# Shema.net
KiCad netlist of a schematic drawn in Altium Designer
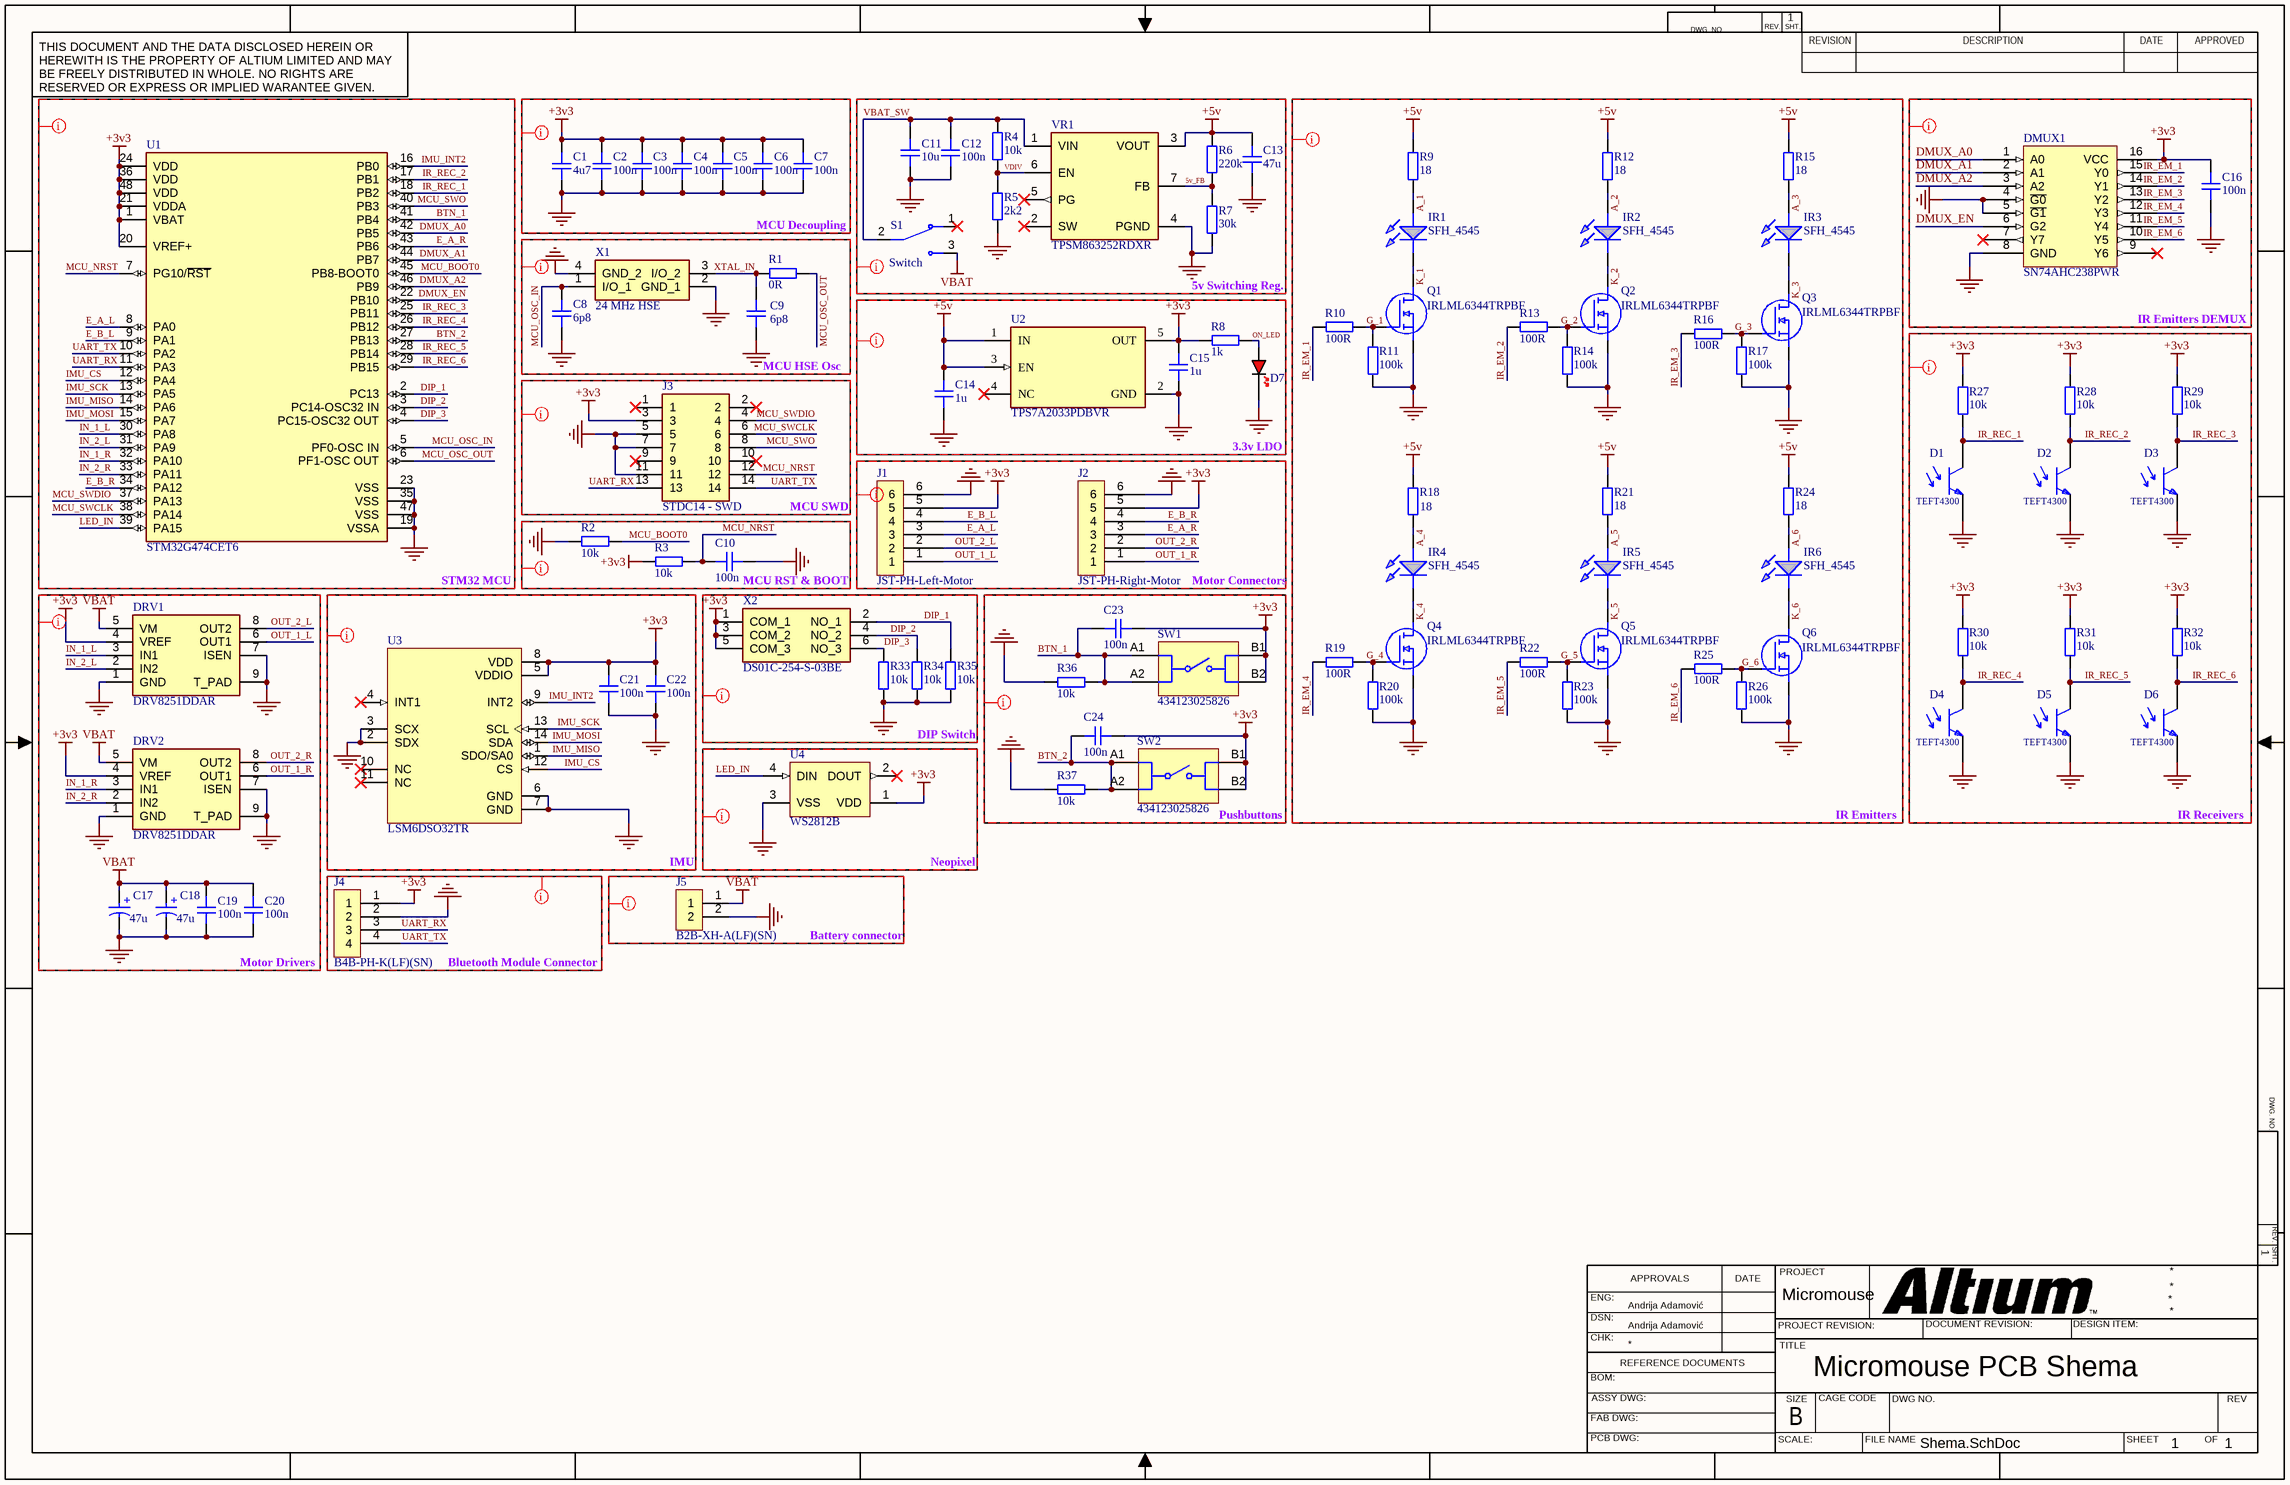
[diagram p0: Shema.SchDoc]

(export (version "E")
  (design (tool "Eeschema 10.0.6"))
  (components
    (comp (ref "C1")
      (value "4u7")
      (footprint "CAP_0603")
      (description "Capacitor SMD 0603")
      (libsource (lib "Schematic-Lib-PhilsLab") (part "CAP_0603"))
    )
    (comp (ref "C2")
      (value "100n")
      (footprint "CAP_0603")
      (description "Capacitor SMD 0603")
      (libsource (lib "Schematic-Lib-PhilsLab") (part "CAP_0603"))
    )
    (comp (ref "C3")
      (value "100n")
      (footprint "CAP_0603")
      (description "Capacitor SMD 0603")
      (libsource (lib "Schematic-Lib-PhilsLab") (part "CAP_0603"))
    )
    (comp (ref "C4")
      (value "100n")
      (footprint "CAP_0603")
      (description "Capacitor SMD 0603")
      (libsource (lib "Schematic-Lib-PhilsLab") (part "CAP_0603"))
    )
    (comp (ref "C5")
      (value "100n")
      (footprint "CAP_0603")
      (description "Capacitor SMD 0603")
      (libsource (lib "Schematic-Lib-PhilsLab") (part "CAP_0603"))
    )
    (comp (ref "C6")
      (value "100n")
      (footprint "CAP_0603")
      (description "Capacitor SMD 0603")
      (libsource (lib "Schematic-Lib-PhilsLab") (part "CAP_0603"))
    )
    (comp (ref "C7")
      (value "100n")
      (footprint "CAP_0603")
      (description "Capacitor SMD 0603")
      (libsource (lib "Schematic-Lib-PhilsLab") (part "CAP_0603"))
    )
    (comp (ref "C8")
      (value "6p8")
      (footprint "CAP_0603")
      (description "Capacitor SMD 0603")
      (libsource (lib "Schematic-Lib-PhilsLab") (part "CAP_0603"))
    )
    (comp (ref "C9")
      (value "6p8")
      (footprint "CAP_0603")
      (description "Capacitor SMD 0603")
      (libsource (lib "Schematic-Lib-PhilsLab") (part "CAP_0603"))
    )
    (comp (ref "C10")
      (value "100n")
      (footprint "CAP_0603")
      (description "Capacitor SMD 0603")
      (libsource (lib "Schematic-Lib-PhilsLab") (part "CAP_0603"))
    )
    (comp (ref "C11")
      (value "10u")
      (footprint "CAP_0805")
      (description "Capacitor SMD 0805")
      (libsource (lib "Schematic-Lib-PhilsLab") (part "CAP_0805"))
    )
    (comp (ref "C12")
      (value "100n")
      (footprint "CAP_0603")
      (description "Capacitor SMD 0603")
      (libsource (lib "Schematic-Lib-PhilsLab") (part "CAP_0603"))
    )
    (comp (ref "C13")
      (value "47u")
      (footprint "CAP_1206")
      (description "Capacitor SMD 1206")
      (libsource (lib "Schematic-Lib-PhilsLab") (part "CAP_1206"))
    )
    (comp (ref "C14")
      (value "1u")
      (footprint "CAP_0805")
      (description "Capacitor SMD 0805")
      (libsource (lib "Schematic-Lib-PhilsLab") (part "CAP_0805"))
    )
    (comp (ref "C15")
      (value "1u")
      (footprint "CAP_0805")
      (description "Capacitor SMD 0805")
      (libsource (lib "Schematic-Lib-PhilsLab") (part "CAP_0805"))
    )
    (comp (ref "C16")
      (value "100n")
      (footprint "CAP_0603")
      (description "Capacitor SMD 0603")
      (libsource (lib "Schematic-Lib-PhilsLab") (part "CAP_0603"))
    )
    (comp (ref "C17")
      (value "47u")
      (footprint "WCAP-ASLI_D6.3H5.5")
      (description "WCAP-ASLI Aluminum Electrolytic Capacitors")
      (fields (field (name "TOLERANCE") "20%"))
      (libsource (lib "Altium Content Vault") (part "Capacitor_Polarized"))
    )
    (comp (ref "C18")
      (value "47u")
      (footprint "WCAP-ASLI_D6.3H5.5")
      (description "WCAP-ASLI Aluminum Electrolytic Capacitors")
      (fields (field (name "TOLERANCE") "20%"))
      (libsource (lib "Altium Content Vault") (part "Capacitor_Polarized"))
    )
    (comp (ref "C19")
      (value "100n")
      (footprint "CAP_0603")
      (description "Capacitor SMD 0603")
      (libsource (lib "Schematic-Lib-PhilsLab") (part "CAP_0603"))
    )
    (comp (ref "C20")
      (value "100n")
      (footprint "CAP_0603")
      (description "Capacitor SMD 0603")
      (libsource (lib "Schematic-Lib-PhilsLab") (part "CAP_0603"))
    )
    (comp (ref "C21")
      (value "100n")
      (footprint "CAP_0603")
      (description "Capacitor SMD 0603")
      (libsource (lib "Schematic-Lib-PhilsLab") (part "CAP_0603"))
    )
    (comp (ref "C22")
      (value "100n")
      (footprint "CAP_0603")
      (description "Capacitor SMD 0603")
      (libsource (lib "Schematic-Lib-PhilsLab") (part "CAP_0603"))
    )
    (comp (ref "C23")
      (value "100n")
      (footprint "CAP_0603")
      (description "Capacitor SMD 0603")
      (libsource (lib "Schematic-Lib-PhilsLab") (part "CAP_0603"))
    )
    (comp (ref "C24")
      (value "100n")
      (footprint "CAP_0603")
      (description "Capacitor SMD 0603")
      (libsource (lib "Schematic-Lib-PhilsLab") (part "CAP_0603"))
    )
    (comp (ref "D1")
      (value "TEFT4300")
      (footprint "FP-6_544-5269_01-4-MFG")
      (description "TEFT4300 PHOTOTRANSISTOR 3.0MM WIDE VIEW / Phototransistor IR Chip Silicon 925nm 2-Pin T-1")
      (libsource (lib "Altium Content Vault") (part "fcf5d96e013ede1c9e051256f92411f"))
    )
    (comp (ref "D2")
      (value "TEFT4300")
      (footprint "FP-6_544-5269_01-4-MFG")
      (description "TEFT4300 PHOTOTRANSISTOR 3.0MM WIDE VIEW / Phototransistor IR Chip Silicon 925nm 2-Pin T-1")
      (libsource (lib "Altium Content Vault") (part "fcf5d96e013ede1c9e051256f92411f"))
    )
    (comp (ref "D3")
      (value "TEFT4300")
      (footprint "FP-6_544-5269_01-4-MFG")
      (description "TEFT4300 PHOTOTRANSISTOR 3.0MM WIDE VIEW / Phototransistor IR Chip Silicon 925nm 2-Pin T-1")
      (libsource (lib "Altium Content Vault") (part "fcf5d96e013ede1c9e051256f92411f"))
    )
    (comp (ref "D4")
      (value "TEFT4300")
      (footprint "FP-6_544-5269_01-4-MFG")
      (description "TEFT4300 PHOTOTRANSISTOR 3.0MM WIDE VIEW / Phototransistor IR Chip Silicon 925nm 2-Pin T-1")
      (libsource (lib "Altium Content Vault") (part "fcf5d96e013ede1c9e051256f92411f"))
    )
    (comp (ref "D5")
      (value "TEFT4300")
      (footprint "FP-6_544-5269_01-4-MFG")
      (description "TEFT4300 PHOTOTRANSISTOR 3.0MM WIDE VIEW / Phototransistor IR Chip Silicon 925nm 2-Pin T-1")
      (libsource (lib "Altium Content Vault") (part "fcf5d96e013ede1c9e051256f92411f"))
    )
    (comp (ref "D6")
      (value "TEFT4300")
      (footprint "FP-6_544-5269_01-4-MFG")
      (description "TEFT4300 PHOTOTRANSISTOR 3.0MM WIDE VIEW / Phototransistor IR Chip Silicon 925nm 2-Pin T-1")
      (libsource (lib "Altium Content Vault") (part "fcf5d96e013ede1c9e051256f92411f"))
    )
    (comp (ref "D7")
      (value "RED")
      (footprint "LED_0603_RED")
      (description "LED 0603 RED SMD")
      (libsource (lib "Schematic-Lib-PhilsLab") (part "LED_0603_RED"))
    )
    (comp (ref "DMUX1")
      (value "SN74AHC238PWR")
      (footprint "TSOP65P640X120-16N")
      (libsource (lib "Andrija Adamovic") (part "SN74AHC238PWR-Symbol-1"))
    )
    (comp (ref "DRV1")
      (value "DRV8251DDAR")
      (footprint "SOIC127P600X170-9N")
      (description "Motor Drives")
      (fields (field (name "MOUSER PART NUMBER") "595-DRV8251DDAR"))
      (libsource (lib "Andrija Adamovic") (part "DRV8251DDAR"))
    )
    (comp (ref "DRV2")
      (value "DRV8251DDAR")
      (footprint "SOIC127P600X170-9N")
      (description "Motor Drives")
      (fields (field (name "MOUSER PART NUMBER") "595-DRV8251DDAR"))
      (libsource (lib "Andrija Adamovic") (part "DRV8251DDAR"))
    )
    (comp (ref "IR1")
      (value "SFH_4545")
      (footprint "SFH4545")
      (description "SFH 4545 Osram Opto, 950nm IR LED, 5 mm Through Hole package")
      (fields
        (field (name "MANUFACTURER_PART_NUMBER") "SFH 4545")
        (field (name "MOUSER PART NUMBER") "720-SFH4545")
      )
      (libsource (lib "Andrija Adamovic") (part "SFH_4545"))
    )
    (comp (ref "IR2")
      (value "SFH_4545")
      (footprint "SFH4545")
      (description "SFH 4545 Osram Opto, 950nm IR LED, 5 mm Through Hole package")
      (fields
        (field (name "MANUFACTURER_PART_NUMBER") "SFH 4545")
        (field (name "MOUSER PART NUMBER") "720-SFH4545")
      )
      (libsource (lib "Andrija Adamovic") (part "SFH_4545"))
    )
    (comp (ref "IR3")
      (value "SFH_4545")
      (footprint "SFH4545")
      (description "SFH 4545 Osram Opto, 950nm IR LED, 5 mm Through Hole package")
      (fields
        (field (name "MANUFACTURER_PART_NUMBER") "SFH 4545")
        (field (name "MOUSER PART NUMBER") "720-SFH4545")
      )
      (libsource (lib "Andrija Adamovic") (part "SFH_4545"))
    )
    (comp (ref "IR4")
      (value "SFH_4545")
      (footprint "SFH4545")
      (description "SFH 4545 Osram Opto, 950nm IR LED, 5 mm Through Hole package")
      (fields
        (field (name "MANUFACTURER_PART_NUMBER") "SFH 4545")
        (field (name "MOUSER PART NUMBER") "720-SFH4545")
      )
      (libsource (lib "Andrija Adamovic") (part "SFH_4545"))
    )
    (comp (ref "IR5")
      (value "SFH_4545")
      (footprint "SFH4545")
      (description "SFH 4545 Osram Opto, 950nm IR LED, 5 mm Through Hole package")
      (fields
        (field (name "MANUFACTURER_PART_NUMBER") "SFH 4545")
        (field (name "MOUSER PART NUMBER") "720-SFH4545")
      )
      (libsource (lib "Andrija Adamovic") (part "SFH_4545"))
    )
    (comp (ref "IR6")
      (value "SFH_4545")
      (footprint "SFH4545")
      (description "SFH 4545 Osram Opto, 950nm IR LED, 5 mm Through Hole package")
      (fields
        (field (name "MANUFACTURER_PART_NUMBER") "SFH 4545")
        (field (name "MOUSER PART NUMBER") "720-SFH4545")
      )
      (libsource (lib "Andrija Adamovic") (part "SFH_4545"))
    )
    (comp (ref "J1")
      (value "JST-PH-Left-Motor")
      (footprint "JST_B6B-PH-K-S(LF)(SN)")
      (description "Socket; wire-board; male; PH; 2mm; PIN: 6; THT; 100V; 2A; -25÷85°C")
      (fields
        (field (name "MF") "{'manufacturer': u'JST Sales America Inc.'}")
        (field (name "MP") "B6B-PH-K-S(LF)(SN)")
      )
      (libsource (lib "Andrija Adamovic") (part "B6B-PH-K-S(LF)(SN)"))
    )
    (comp (ref "J2")
      (value "JST-PH-Right-Motor")
      (footprint "JST_B6B-PH-K-S(LF)(SN)")
      (description "Socket; wire-board; male; PH; 2mm; PIN: 6; THT; 100V; 2A; -25÷85°C")
      (fields
        (field (name "MF") "{'manufacturer': u'JST Sales America Inc.'}")
        (field (name "MP") "B6B-PH-K-S(LF)(SN)")
      )
      (libsource (lib "Andrija Adamovic") (part "B6B-PH-K-S(LF)(SN)"))
    )
    (comp (ref "J3")
      (value "STDC14 - SWD")
      (footprint "FTSH10701LDVKTR")
      (description "Conn Unshrouded Header HDR 14 POS 1.27mm Solder ST Top Entry SMD TIGER CLAW T/R")
      (fields
        (field (name "MOUSER PART NUMBER") "200-FTSH10701LDVKTR")
        (field (name "MANUFACTURER_PART_NUMBER") "FTSH-107-01-L-DV-K-TR")
      )
      (libsource (lib "Andrija Adamovic") (part "FTSH-107-01-L-DV-K-TR"))
    )
    (comp (ref "J4")
      (value "B4B-PH-K(LF)(SN)")
      (footprint "FP-B4B-PH-K_LF_SN-MFG")
      (description "Conn Shrouded Header (4 Sides) HDR 4 POS 2mm Solder ST Thru-Hole Box")
      (libsource (lib "Andrija Adamovic") (part "B4B-PH-K(LF)(SN)"))
    )
    (comp (ref "J5")
      (value "B2B-XH-A(LF)(SN)")
      (footprint "FP-B2B-XH-A_LF_SN-MFG")
      (description "CONNECTOR HEADER, XH SERIES, 2 POSITION, 2.50MM, Press-Fit Solder, Detent Lock, Natural")
      (libsource (lib "Andrija Adamovic") (part "B2B-XH-A(LF)(SN)"))
    )
    (comp (ref "Q1")
      (value "IRLML6344TRPBF")
      (footprint "SOT95P237X112-3N")
      (description "IRLML6344TRPBF N-channel MOSFET Transistor, 5 A, 30 V, 3-Pin SOT-23")
      (fields (field (name "MOUSER PART NUMBER") "942-IRLML6344TRPBF"))
      (libsource (lib "Andrija Adamovic") (part "IRLML6344TRPBF"))
    )
    (comp (ref "Q2")
      (value "IRLML6344TRPBF")
      (footprint "SOT95P237X112-3N")
      (description "IRLML6344TRPBF N-channel MOSFET Transistor, 5 A, 30 V, 3-Pin SOT-23")
      (fields (field (name "MOUSER PART NUMBER") "942-IRLML6344TRPBF"))
      (libsource (lib "Andrija Adamovic") (part "IRLML6344TRPBF"))
    )
    (comp (ref "Q3")
      (value "IRLML6344TRPBF")
      (footprint "SOT95P237X112-3N")
      (description "IRLML6344TRPBF N-channel MOSFET Transistor, 5 A, 30 V, 3-Pin SOT-23")
      (fields (field (name "MOUSER PART NUMBER") "942-IRLML6344TRPBF"))
      (libsource (lib "Andrija Adamovic") (part "IRLML6344TRPBF"))
    )
    (comp (ref "Q4")
      (value "IRLML6344TRPBF")
      (footprint "SOT95P237X112-3N")
      (description "IRLML6344TRPBF N-channel MOSFET Transistor, 5 A, 30 V, 3-Pin SOT-23")
      (fields (field (name "MOUSER PART NUMBER") "942-IRLML6344TRPBF"))
      (libsource (lib "Andrija Adamovic") (part "IRLML6344TRPBF"))
    )
    (comp (ref "Q5")
      (value "IRLML6344TRPBF")
      (footprint "SOT95P237X112-3N")
      (description "IRLML6344TRPBF N-channel MOSFET Transistor, 5 A, 30 V, 3-Pin SOT-23")
      (fields (field (name "MOUSER PART NUMBER") "942-IRLML6344TRPBF"))
      (libsource (lib "Andrija Adamovic") (part "IRLML6344TRPBF"))
    )
    (comp (ref "Q6")
      (value "IRLML6344TRPBF")
      (footprint "SOT95P237X112-3N")
      (description "IRLML6344TRPBF N-channel MOSFET Transistor, 5 A, 30 V, 3-Pin SOT-23")
      (fields (field (name "MOUSER PART NUMBER") "942-IRLML6344TRPBF"))
      (libsource (lib "Andrija Adamovic") (part "IRLML6344TRPBF"))
    )
    (comp (ref "R1")
      (value "0R")
      (footprint "RES_0402")
      (description "Resistor SMD 0402")
      (libsource (lib "Schematic-Lib-PhilsLab") (part "RES_0402"))
    )
    (comp (ref "R2")
      (value "10k")
      (footprint "RES_0603")
      (description "Resistor SMD 0603")
      (libsource (lib "Schematic-Lib-PhilsLab") (part "RES_0603"))
    )
    (comp (ref "R3")
      (value "10k")
      (footprint "RES_0603")
      (description "Resistor SMD 0603")
      (libsource (lib "Schematic-Lib-PhilsLab") (part "RES_0603"))
    )
    (comp (ref "R4")
      (value "10k")
      (footprint "RES_0603")
      (description "Resistor SMD 0603")
      (libsource (lib "Schematic-Lib-PhilsLab") (part "RES_0603"))
    )
    (comp (ref "R5")
      (value "2k2")
      (footprint "RES_0603")
      (description "Resistor SMD 0603")
      (libsource (lib "Schematic-Lib-PhilsLab") (part "RES_0603"))
    )
    (comp (ref "R6")
      (value "220k")
      (footprint "RES_0603")
      (description "Resistor SMD 0603")
      (libsource (lib "Schematic-Lib-PhilsLab") (part "RES_0603"))
    )
    (comp (ref "R7")
      (value "30k")
      (footprint "RES_0603")
      (description "Resistor SMD 0603")
      (libsource (lib "Schematic-Lib-PhilsLab") (part "RES_0603"))
    )
    (comp (ref "R8")
      (value "1k")
      (footprint "RES_0603")
      (description "Resistor SMD 0603")
      (libsource (lib "Schematic-Lib-PhilsLab") (part "RES_0603"))
    )
    (comp (ref "R9")
      (value "18")
      (footprint "RES_1206")
      (description "Resistor SMD 1206")
      (libsource (lib "Schematic-Lib-PhilsLab") (part "RES_1206"))
    )
    (comp (ref "R10")
      (value "100R")
      (footprint "RES_0603")
      (description "Resistor SMD 0603")
      (libsource (lib "Schematic-Lib-PhilsLab") (part "RES_0603"))
    )
    (comp (ref "R11")
      (value "100k")
      (footprint "RES_0603")
      (description "Resistor SMD 0603")
      (libsource (lib "Schematic-Lib-PhilsLab") (part "RES_0603"))
    )
    (comp (ref "R12")
      (value "18")
      (footprint "RES_1206")
      (description "Resistor SMD 1206")
      (libsource (lib "Schematic-Lib-PhilsLab") (part "RES_1206"))
    )
    (comp (ref "R13")
      (value "100R")
      (footprint "RES_0603")
      (description "Resistor SMD 0603")
      (libsource (lib "Schematic-Lib-PhilsLab") (part "RES_0603"))
    )
    (comp (ref "R14")
      (value "100k")
      (footprint "RES_0603")
      (description "Resistor SMD 0603")
      (libsource (lib "Schematic-Lib-PhilsLab") (part "RES_0603"))
    )
    (comp (ref "R15")
      (value "18")
      (footprint "RES_1206")
      (description "Resistor SMD 1206")
      (libsource (lib "Schematic-Lib-PhilsLab") (part "RES_1206"))
    )
    (comp (ref "R16")
      (value "100R")
      (footprint "RES_0603")
      (description "Resistor SMD 0603")
      (libsource (lib "Schematic-Lib-PhilsLab") (part "RES_0603"))
    )
    (comp (ref "R17")
      (value "100k")
      (footprint "RES_0603")
      (description "Resistor SMD 0603")
      (libsource (lib "Schematic-Lib-PhilsLab") (part "RES_0603"))
    )
    (comp (ref "R18")
      (value "18")
      (footprint "RES_1206")
      (description "Resistor SMD 1206")
      (libsource (lib "Schematic-Lib-PhilsLab") (part "RES_1206"))
    )
    (comp (ref "R19")
      (value "100R")
      (footprint "RES_0603")
      (description "Resistor SMD 0603")
      (libsource (lib "Schematic-Lib-PhilsLab") (part "RES_0603"))
    )
    (comp (ref "R20")
      (value "100k")
      (footprint "RES_0603")
      (description "Resistor SMD 0603")
      (libsource (lib "Schematic-Lib-PhilsLab") (part "RES_0603"))
    )
    (comp (ref "R21")
      (value "18")
      (footprint "RES_1206")
      (description "Resistor SMD 1206")
      (libsource (lib "Schematic-Lib-PhilsLab") (part "RES_1206"))
    )
    (comp (ref "R22")
      (value "100R")
      (footprint "RES_0603")
      (description "Resistor SMD 0603")
      (libsource (lib "Schematic-Lib-PhilsLab") (part "RES_0603"))
    )
    (comp (ref "R23")
      (value "100k")
      (footprint "RES_0603")
      (description "Resistor SMD 0603")
      (libsource (lib "Schematic-Lib-PhilsLab") (part "RES_0603"))
    )
    (comp (ref "R24")
      (value "18")
      (footprint "RES_1206")
      (description "Resistor SMD 1206")
      (libsource (lib "Schematic-Lib-PhilsLab") (part "RES_1206"))
    )
    (comp (ref "R25")
      (value "100R")
      (footprint "RES_0603")
      (description "Resistor SMD 0603")
      (libsource (lib "Schematic-Lib-PhilsLab") (part "RES_0603"))
    )
    (comp (ref "R26")
      (value "100k")
      (footprint "RES_0603")
      (description "Resistor SMD 0603")
      (libsource (lib "Schematic-Lib-PhilsLab") (part "RES_0603"))
    )
    (comp (ref "R27")
      (value "10k")
      (footprint "RES_0603")
      (description "Resistor SMD 0603")
      (libsource (lib "Schematic-Lib-PhilsLab") (part "RES_0603"))
    )
    (comp (ref "R28")
      (value "10k")
      (footprint "RES_0603")
      (description "Resistor SMD 0603")
      (libsource (lib "Schematic-Lib-PhilsLab") (part "RES_0603"))
    )
    (comp (ref "R29")
      (value "10k")
      (footprint "RES_0603")
      (description "Resistor SMD 0603")
      (libsource (lib "Schematic-Lib-PhilsLab") (part "RES_0603"))
    )
    (comp (ref "R30")
      (value "10k")
      (footprint "RES_0603")
      (description "Resistor SMD 0603")
      (libsource (lib "Schematic-Lib-PhilsLab") (part "RES_0603"))
    )
    (comp (ref "R31")
      (value "10k")
      (footprint "RES_0603")
      (description "Resistor SMD 0603")
      (libsource (lib "Schematic-Lib-PhilsLab") (part "RES_0603"))
    )
    (comp (ref "R32")
      (value "10k")
      (footprint "RES_0603")
      (description "Resistor SMD 0603")
      (libsource (lib "Schematic-Lib-PhilsLab") (part "RES_0603"))
    )
    (comp (ref "R33")
      (value "10k")
      (footprint "RES_0603")
      (description "Resistor SMD 0603")
      (libsource (lib "Schematic-Lib-PhilsLab") (part "RES_0603"))
    )
    (comp (ref "R34")
      (value "10k")
      (footprint "RES_0603")
      (description "Resistor SMD 0603")
      (libsource (lib "Schematic-Lib-PhilsLab") (part "RES_0603"))
    )
    (comp (ref "R35")
      (value "10k")
      (footprint "RES_0603")
      (description "Resistor SMD 0603")
      (libsource (lib "Schematic-Lib-PhilsLab") (part "RES_0603"))
    )
    (comp (ref "R36")
      (value "10k")
      (footprint "RES_0603")
      (description "Resistor SMD 0603")
      (libsource (lib "Schematic-Lib-PhilsLab") (part "RES_0603"))
    )
    (comp (ref "R37")
      (value "10k")
      (footprint "RES_0603")
      (description "Resistor SMD 0603")
      (libsource (lib "Schematic-Lib-PhilsLab") (part "RES_0603"))
    )
    (comp (ref "S1")
      (value "Switch")
      (footprint "SW_SLW-864574-5A-RA-N-D")
      (description "8.6 x 4.5 x 6.2 mm, 5 mm Raised Slide Actuator, Right Angle, Through Hole, Slide Switch")
      (fields
        (field (name "MP") "SLW-864574-5A-RA-N-D")
        (field (name "MF") "{'manufacturer': u'Same Sky (Formerly CUI Devices)'}")
      )
      (libsource (lib "Andrija Adamovic") (part "SLW-864574-5A-RA-N-D"))
    )
    (comp (ref "SW1")
      (value "434123025826")
      (footprint "434123025826")
      (description "Tactile Switch, 0.05A, 16Vdc, 260Gf, Smd Rohs Compliant: Yes")
      (libsource (lib "Andrija Adamovic") (part "SPST-NO_4P"))
    )
    (comp (ref "SW2")
      (value "434123025826")
      (footprint "434123025826")
      (description "Tactile Switch, 0.05A, 16Vdc, 260Gf, Smd Rohs Compliant: Yes")
      (libsource (lib "Andrija Adamovic") (part "SPST-NO_4P"))
    )
    (comp (ref "U1")
      (value "STM32G474CET6")
      (footprint "FP-STM32G474CET6-MFG")
      (description "MAINSTREAM ARM CORTEX-M4 CORE WI")
      (fields
        (field (name "OCTOPART") "https://octopart.com/stm32g474cet6-stmicroelectronics-99072248")
        (field (name "MANUFACTURER") "STMicroelectronics")
      )
      (libsource (lib "Altium Content Vault") (part "96d063d3108c84c79c2ea684d87d0dc"))
    )
    (comp (ref "U2")
      (value "TPS7A2033PDBVR")
      (footprint "FP-DBV0005A-MFG")
      (description "IC REG LINEAR 3.3V 300MA SOT23-5")
      (libsource (lib "Altium Content Vault") (part "76aa7ad0ceb1012e0d85aeafc53095f"))
    )
    (comp (ref "U3")
      (value "LSM6DSO32TR")
      (footprint "XDCR_LSM6DSO32TR")
      (description "Accelerometer, Gyroscope, Temperature, 6 Axis Sensor IÂ²C, SPI Output")
      (fields (field (name "MF") "STMicroelectronics"))
      (libsource (lib "Andrija Adamovic") (part "LSM6DSO32TR"))
    )
    (comp (ref "U4")
      (value "WS2812B")
      (footprint "ADAI-WS2812B_V")
      (fields (field (name "MANUFACTURER") "Adafruit Industries"))
      (libsource (lib "Andrija Adamovic") (part "ADAI-WS2812B-4"))
    )
    (comp (ref "VR1")
      (value "TPSM863252RDXR")
      (footprint "VREG_TPSM863252RDXR")
      (description "3-V to 17-V input voltage, 3-A Eco-mode synchronous buck module")
      (fields (field (name "MF") "Texas Instruments"))
      (libsource (lib "Andrija Adamovic") (part "TPSM863252RDXR"))
    )
    (comp (ref "X1")
      (value "24 MHz HSE")
      (footprint "CX2016FB24000B0FZZH1")
      (description "Crystals 2.0x1.6mm 24MHz 6pF - 40 C to + 85 C 50 Ohms")
      (fields (field (name "MANUFACTURER_PART_NUMBER") "CX2016FB24000B0FZZH1"))
      (libsource (lib "Andrija Adamovic") (part "CX2016FB24000B0FZZH1"))
    )
    (comp (ref "X2")
      (value "DS01C-254-S-03BE")
      (footprint "DS01C254S03BE")
      (fields (field (name "MOUSER PART NUMBER") "490-DS01C-254-S-03BE"))
      (libsource (lib "Andrija Adamovic") (part "DS01C-254-S-03BE"))
    )
  )
  (nets
    (net (code "1") (name "+3v3") (class "Default")
      (node (ref "C1") (pin "2") (pinfunction "2_2") (pintype "passive"))
      (node (ref "C15") (pin "2") (pinfunction "2_2") (pintype "passive"))
      (node (ref "C16") (pin "2") (pinfunction "2_2") (pintype "passive"))
      (node (ref "C2") (pin "2") (pinfunction "2_2") (pintype "passive"))
      (node (ref "C21") (pin "1") (pinfunction "1_1") (pintype "passive"))
      (node (ref "C22") (pin "1") (pinfunction "1_1") (pintype "passive"))
      (node (ref "C23") (pin "1") (pinfunction "1_1") (pintype "passive"))
      (node (ref "C24") (pin "1") (pinfunction "1_1") (pintype "passive"))
      (node (ref "C3") (pin "2") (pinfunction "2_2") (pintype "passive"))
      (node (ref "C4") (pin "2") (pinfunction "2_2") (pintype "passive"))
      (node (ref "C5") (pin "2") (pinfunction "2_2") (pintype "passive"))
      (node (ref "C6") (pin "2") (pinfunction "2_2") (pintype "passive"))
      (node (ref "C7") (pin "2") (pinfunction "2_2") (pintype "passive"))
      (node (ref "DMUX1") (pin "16") (pinfunction "VCC_16") (pintype "power_in"))
      (node (ref "DRV1") (pin "4") (pinfunction "VREF_4") (pintype "passive"))
      (node (ref "DRV2") (pin "4") (pinfunction "VREF_4") (pintype "passive"))
      (node (ref "J1") (pin "5") (pinfunction "5_5") (pintype "passive"))
      (node (ref "J2") (pin "5") (pinfunction "5_5") (pintype "passive"))
      (node (ref "J3") (pin "3") (pinfunction "3_3") (pintype "passive"))
      (node (ref "J4") (pin "1") (pinfunction "1_1") (pintype "passive"))
      (node (ref "R27") (pin "2") (pinfunction "2_2") (pintype "passive"))
      (node (ref "R28") (pin "2") (pinfunction "2_2") (pintype "passive"))
      (node (ref "R29") (pin "2") (pinfunction "2_2") (pintype "passive"))
      (node (ref "R3") (pin "1") (pinfunction "1_1") (pintype "passive"))
      (node (ref "R30") (pin "2") (pinfunction "2_2") (pintype "passive"))
      (node (ref "R31") (pin "2") (pinfunction "2_2") (pintype "passive"))
      (node (ref "R32") (pin "2") (pinfunction "2_2") (pintype "passive"))
      (node (ref "R8") (pin "2") (pinfunction "2_2") (pintype "passive"))
      (node (ref "SW1") (pin "B1") (pinfunction "B1_B1") (pintype "passive"))
      (node (ref "SW1") (pin "B2") (pinfunction "B2_B2") (pintype "passive"))
      (node (ref "SW2") (pin "B1") (pinfunction "B1_B1") (pintype "passive"))
      (node (ref "SW2") (pin "B2") (pinfunction "B2_B2") (pintype "passive"))
      (node (ref "U1") (pin "1") (pinfunction "VBAT_1") (pintype "power_in"))
      (node (ref "U1") (pin "20") (pinfunction "VREF+_20") (pintype "power_in"))
      (node (ref "U1") (pin "21") (pinfunction "VDDA_21") (pintype "power_in"))
      (node (ref "U1") (pin "24") (pinfunction "VDD_24") (pintype "power_in"))
      (node (ref "U1") (pin "36") (pinfunction "VDD_36") (pintype "power_in"))
      (node (ref "U1") (pin "48") (pinfunction "VDD_48") (pintype "power_in"))
      (node (ref "U2") (pin "5") (pinfunction "OUT_5") (pintype "passive"))
      (node (ref "U3") (pin "5") (pinfunction "VDDIO_5") (pintype "power_in"))
      (node (ref "U3") (pin "8") (pinfunction "VDD_8") (pintype "power_in"))
      (node (ref "U4") (pin "1") (pinfunction "VDD_1") (pintype "power_in"))
      (node (ref "X2") (pin "1") (pinfunction "COM_1_1") (pintype "passive"))
      (node (ref "X2") (pin "3") (pinfunction "COM_2_3") (pintype "passive"))
      (node (ref "X2") (pin "5") (pinfunction "COM_3_5") (pintype "passive"))
    )
    (net (code "2") (name "+5v") (class "Default")
      (node (ref "C13") (pin "2") (pinfunction "2_2") (pintype "passive"))
      (node (ref "C14") (pin "2") (pinfunction "2_2") (pintype "passive"))
      (node (ref "R12") (pin "2") (pinfunction "2_2") (pintype "passive"))
      (node (ref "R15") (pin "2") (pinfunction "2_2") (pintype "passive"))
      (node (ref "R18") (pin "2") (pinfunction "2_2") (pintype "passive"))
      (node (ref "R21") (pin "2") (pinfunction "2_2") (pintype "passive"))
      (node (ref "R24") (pin "2") (pinfunction "2_2") (pintype "passive"))
      (node (ref "R6") (pin "2") (pinfunction "2_2") (pintype "passive"))
      (node (ref "R9") (pin "2") (pinfunction "2_2") (pintype "passive"))
      (node (ref "U2") (pin "1") (pinfunction "IN_1") (pintype "power_in"))
      (node (ref "U2") (pin "3") (pinfunction "EN_3") (pintype "input"))
      (node (ref "VR1") (pin "3") (pinfunction "VOUT_3") (pintype "power_in"))
    )
    (net (code "3") (name "/5v_FB") (class "Default")
      (node (ref "R6") (pin "1") (pinfunction "1_1") (pintype "passive"))
      (node (ref "R7") (pin "2") (pinfunction "2_2") (pintype "passive"))
      (node (ref "VR1") (pin "7") (pinfunction "FB_7") (pintype "passive"))
    )
    (net (code "4") (name "/A_1") (class "Default")
      (node (ref "IR1") (pin "2") (pinfunction "A_2") (pintype "passive"))
      (node (ref "R9") (pin "1") (pinfunction "1_1") (pintype "passive"))
    )
    (net (code "5") (name "/A_2") (class "Default")
      (node (ref "IR2") (pin "2") (pinfunction "A_2") (pintype "passive"))
      (node (ref "R12") (pin "1") (pinfunction "1_1") (pintype "passive"))
    )
    (net (code "6") (name "/A_3") (class "Default")
      (node (ref "IR3") (pin "2") (pinfunction "A_2") (pintype "passive"))
      (node (ref "R15") (pin "1") (pinfunction "1_1") (pintype "passive"))
    )
    (net (code "7") (name "/A_4") (class "Default")
      (node (ref "IR4") (pin "2") (pinfunction "A_2") (pintype "passive"))
      (node (ref "R18") (pin "1") (pinfunction "1_1") (pintype "passive"))
    )
    (net (code "8") (name "/A_5") (class "Default")
      (node (ref "IR5") (pin "2") (pinfunction "A_2") (pintype "passive"))
      (node (ref "R21") (pin "1") (pinfunction "1_1") (pintype "passive"))
    )
    (net (code "9") (name "/A_6") (class "Default")
      (node (ref "IR6") (pin "2") (pinfunction "A_2") (pintype "passive"))
      (node (ref "R24") (pin "1") (pinfunction "1_1") (pintype "passive"))
    )
    (net (code "10") (name "/BTN_1") (class "Default")
      (node (ref "C23") (pin "2") (pinfunction "2_2") (pintype "passive"))
      (node (ref "R36") (pin "2") (pinfunction "2_2") (pintype "passive"))
      (node (ref "SW1") (pin "A1") (pinfunction "A1_A1") (pintype "passive"))
      (node (ref "SW1") (pin "A2") (pinfunction "A2_A2") (pintype "passive"))
      (node (ref "U1") (pin "41") (pinfunction "PB4_41") (pintype "bidirectional"))
    )
    (net (code "11") (name "/BTN_2") (class "Default")
      (node (ref "C24") (pin "2") (pinfunction "2_2") (pintype "passive"))
      (node (ref "R37") (pin "2") (pinfunction "2_2") (pintype "passive"))
      (node (ref "SW2") (pin "A1") (pinfunction "A1_A1") (pintype "passive"))
      (node (ref "SW2") (pin "A2") (pinfunction "A2_A2") (pintype "passive"))
      (node (ref "U1") (pin "27") (pinfunction "PB13_27") (pintype "bidirectional"))
    )
    (net (code "12") (name "/DIP_1") (class "Default")
      (node (ref "R35") (pin "2") (pinfunction "2_2") (pintype "passive"))
      (node (ref "U1") (pin "2") (pinfunction "PC13_2") (pintype "bidirectional"))
      (node (ref "X2") (pin "2") (pinfunction "NO_1_2") (pintype "passive"))
    )
    (net (code "13") (name "/DIP_2") (class "Default")
      (node (ref "R34") (pin "2") (pinfunction "2_2") (pintype "passive"))
      (node (ref "U1") (pin "3") (pinfunction "PC14-OSC32_IN_3") (pintype "bidirectional"))
      (node (ref "X2") (pin "4") (pinfunction "NO_2_4") (pintype "passive"))
    )
    (net (code "14") (name "/DIP_3") (class "Default")
      (node (ref "R33") (pin "2") (pinfunction "2_2") (pintype "passive"))
      (node (ref "U1") (pin "4") (pinfunction "PC15-OSC32_OUT_4") (pintype "bidirectional"))
      (node (ref "X2") (pin "6") (pinfunction "NO_3_6") (pintype "passive"))
    )
    (net (code "15") (name "/DMUX_A0") (class "Default")
      (node (ref "DMUX1") (pin "1") (pinfunction "A0_1") (pintype "input"))
      (node (ref "U1") (pin "42") (pinfunction "PB5_42") (pintype "bidirectional"))
    )
    (net (code "16") (name "/DMUX_A1") (class "Default")
      (node (ref "DMUX1") (pin "2") (pinfunction "A1_2") (pintype "input"))
      (node (ref "U1") (pin "44") (pinfunction "PB7_44") (pintype "bidirectional"))
    )
    (net (code "17") (name "/DMUX_A2") (class "Default")
      (node (ref "DMUX1") (pin "3") (pinfunction "A2_3") (pintype "input"))
      (node (ref "U1") (pin "46") (pinfunction "PB9_46") (pintype "bidirectional"))
    )
    (net (code "18") (name "/DMUX_EN") (class "Default")
      (node (ref "DMUX1") (pin "6") (pinfunction "G2_6") (pintype "input"))
      (node (ref "U1") (pin "22") (pinfunction "PB10_22") (pintype "bidirectional"))
    )
    (net (code "19") (name "/E_A_L") (class "Default")
      (node (ref "J1") (pin "3") (pinfunction "3_3") (pintype "passive"))
      (node (ref "U1") (pin "8") (pinfunction "PA0_8") (pintype "bidirectional"))
    )
    (net (code "20") (name "/E_A_R") (class "Default")
      (node (ref "J2") (pin "3") (pinfunction "3_3") (pintype "passive"))
      (node (ref "U1") (pin "43") (pinfunction "PB6_43") (pintype "bidirectional"))
    )
    (net (code "21") (name "/E_B_L") (class "Default")
      (node (ref "J1") (pin "4") (pinfunction "4_4") (pintype "passive"))
      (node (ref "U1") (pin "9") (pinfunction "PA1_9") (pintype "bidirectional"))
    )
    (net (code "22") (name "/E_B_R") (class "Default")
      (node (ref "J2") (pin "4") (pinfunction "4_4") (pintype "passive"))
      (node (ref "U1") (pin "34") (pinfunction "PA12_34") (pintype "bidirectional"))
    )
    (net (code "23") (name "/G_1") (class "Default")
      (node (ref "Q1") (pin "1") (pinfunction "G_1") (pintype "passive"))
      (node (ref "R10") (pin "2") (pinfunction "2_2") (pintype "passive"))
      (node (ref "R11") (pin "2") (pinfunction "2_2") (pintype "passive"))
    )
    (net (code "24") (name "/G_2") (class "Default")
      (node (ref "Q2") (pin "1") (pinfunction "G_1") (pintype "passive"))
      (node (ref "R13") (pin "2") (pinfunction "2_2") (pintype "passive"))
      (node (ref "R14") (pin "2") (pinfunction "2_2") (pintype "passive"))
    )
    (net (code "25") (name "/G_3") (class "Default")
      (node (ref "Q3") (pin "1") (pinfunction "G_1") (pintype "passive"))
      (node (ref "R16") (pin "2") (pinfunction "2_2") (pintype "passive"))
      (node (ref "R17") (pin "2") (pinfunction "2_2") (pintype "passive"))
    )
    (net (code "26") (name "/G_4") (class "Default")
      (node (ref "Q4") (pin "1") (pinfunction "G_1") (pintype "passive"))
      (node (ref "R19") (pin "2") (pinfunction "2_2") (pintype "passive"))
      (node (ref "R20") (pin "2") (pinfunction "2_2") (pintype "passive"))
    )
    (net (code "27") (name "/G_5") (class "Default")
      (node (ref "Q5") (pin "1") (pinfunction "G_1") (pintype "passive"))
      (node (ref "R22") (pin "2") (pinfunction "2_2") (pintype "passive"))
      (node (ref "R23") (pin "2") (pinfunction "2_2") (pintype "passive"))
    )
    (net (code "28") (name "/G_6") (class "Default")
      (node (ref "Q6") (pin "1") (pinfunction "G_1") (pintype "passive"))
      (node (ref "R25") (pin "2") (pinfunction "2_2") (pintype "passive"))
      (node (ref "R26") (pin "2") (pinfunction "2_2") (pintype "passive"))
    )
    (net (code "29") (name "/IMU_CS") (class "Default")
      (node (ref "U1") (pin "12") (pinfunction "PA4_12") (pintype "bidirectional"))
      (node (ref "U3") (pin "12") (pinfunction "CS_12") (pintype "input"))
    )
    (net (code "30") (name "/IMU_INT2") (class "Default")
      (node (ref "U1") (pin "16") (pinfunction "PB0_16") (pintype "bidirectional"))
      (node (ref "U3") (pin "9") (pinfunction "INT2_9") (pintype "bidirectional"))
    )
    (net (code "31") (name "/IMU_MISO") (class "Default")
      (node (ref "U1") (pin "14") (pinfunction "PA6_14") (pintype "bidirectional"))
      (node (ref "U3") (pin "1") (pinfunction "SDO/SA0_1") (pintype "bidirectional"))
    )
    (net (code "32") (name "/IMU_MOSI") (class "Default")
      (node (ref "U1") (pin "15") (pinfunction "PA7_15") (pintype "bidirectional"))
      (node (ref "U3") (pin "14") (pinfunction "SDA_14") (pintype "bidirectional"))
    )
    (net (code "33") (name "/IMU_SCK") (class "Default")
      (node (ref "U1") (pin "13") (pinfunction "PA5_13") (pintype "bidirectional"))
      (node (ref "U3") (pin "13") (pinfunction "SCL_13") (pintype "input"))
    )
    (net (code "34") (name "/IN_1_L") (class "Default")
      (node (ref "DRV1") (pin "3") (pinfunction "IN1_3") (pintype "passive"))
      (node (ref "U1") (pin "30") (pinfunction "PA8_30") (pintype "bidirectional"))
    )
    (net (code "35") (name "/IN_1_R") (class "Default")
      (node (ref "DRV2") (pin "3") (pinfunction "IN1_3") (pintype "passive"))
      (node (ref "U1") (pin "32") (pinfunction "PA10_32") (pintype "bidirectional"))
    )
    (net (code "36") (name "/IN_2_L") (class "Default")
      (node (ref "DRV1") (pin "2") (pinfunction "IN2_2") (pintype "passive"))
      (node (ref "U1") (pin "31") (pinfunction "PA9_31") (pintype "bidirectional"))
    )
    (net (code "37") (name "/IN_2_R") (class "Default")
      (node (ref "DRV2") (pin "2") (pinfunction "IN2_2") (pintype "passive"))
      (node (ref "U1") (pin "33") (pinfunction "PA11_33") (pintype "bidirectional"))
    )
    (net (code "38") (name "/IR_EM_1") (class "Default")
      (node (ref "DMUX1") (pin "15") (pinfunction "Y0_15") (pintype "output"))
      (node (ref "R10") (pin "1") (pinfunction "1_1") (pintype "passive"))
    )
    (net (code "39") (name "/IR_EM_2") (class "Default")
      (node (ref "DMUX1") (pin "14") (pinfunction "Y1_14") (pintype "output"))
      (node (ref "R13") (pin "1") (pinfunction "1_1") (pintype "passive"))
    )
    (net (code "40") (name "/IR_EM_3") (class "Default")
      (node (ref "DMUX1") (pin "13") (pinfunction "Y2_13") (pintype "output"))
      (node (ref "R16") (pin "1") (pinfunction "1_1") (pintype "passive"))
    )
    (net (code "41") (name "/IR_EM_4") (class "Default")
      (node (ref "DMUX1") (pin "12") (pinfunction "Y3_12") (pintype "output"))
      (node (ref "R19") (pin "1") (pinfunction "1_1") (pintype "passive"))
    )
    (net (code "42") (name "/IR_EM_5") (class "Default")
      (node (ref "DMUX1") (pin "11") (pinfunction "Y4_11") (pintype "output"))
      (node (ref "R22") (pin "1") (pinfunction "1_1") (pintype "passive"))
    )
    (net (code "43") (name "/IR_EM_6") (class "Default")
      (node (ref "DMUX1") (pin "10") (pinfunction "Y5_10") (pintype "output"))
      (node (ref "R25") (pin "1") (pinfunction "1_1") (pintype "passive"))
    )
    (net (code "44") (name "/IR_REC_1") (class "Default")
      (node (ref "D1") (pin "2") (pinfunction "C_2") (pintype "passive"))
      (node (ref "R27") (pin "1") (pinfunction "1_1") (pintype "passive"))
      (node (ref "U1") (pin "18") (pinfunction "PB2_18") (pintype "bidirectional"))
    )
    (net (code "45") (name "/IR_REC_2") (class "Default")
      (node (ref "D2") (pin "2") (pinfunction "C_2") (pintype "passive"))
      (node (ref "R28") (pin "1") (pinfunction "1_1") (pintype "passive"))
      (node (ref "U1") (pin "17") (pinfunction "PB1_17") (pintype "bidirectional"))
    )
    (net (code "46") (name "/IR_REC_3") (class "Default")
      (node (ref "D3") (pin "2") (pinfunction "C_2") (pintype "passive"))
      (node (ref "R29") (pin "1") (pinfunction "1_1") (pintype "passive"))
      (node (ref "U1") (pin "25") (pinfunction "PB11_25") (pintype "bidirectional"))
    )
    (net (code "47") (name "/IR_REC_4") (class "Default")
      (node (ref "D4") (pin "2") (pinfunction "C_2") (pintype "passive"))
      (node (ref "R30") (pin "1") (pinfunction "1_1") (pintype "passive"))
      (node (ref "U1") (pin "26") (pinfunction "PB12_26") (pintype "bidirectional"))
    )
    (net (code "48") (name "/IR_REC_5") (class "Default")
      (node (ref "D5") (pin "2") (pinfunction "C_2") (pintype "passive"))
      (node (ref "R31") (pin "1") (pinfunction "1_1") (pintype "passive"))
      (node (ref "U1") (pin "28") (pinfunction "PB14_28") (pintype "bidirectional"))
    )
    (net (code "49") (name "/IR_REC_6") (class "Default")
      (node (ref "D6") (pin "2") (pinfunction "C_2") (pintype "passive"))
      (node (ref "R32") (pin "1") (pinfunction "1_1") (pintype "passive"))
      (node (ref "U1") (pin "29") (pinfunction "PB15_29") (pintype "bidirectional"))
    )
    (net (code "50") (name "/K_1") (class "Default")
      (node (ref "IR1") (pin "1") (pinfunction "K_1") (pintype "passive"))
      (node (ref "Q1") (pin "3") (pinfunction "D_3") (pintype "passive"))
    )
    (net (code "51") (name "/K_2") (class "Default")
      (node (ref "IR2") (pin "1") (pinfunction "K_1") (pintype "passive"))
      (node (ref "Q2") (pin "3") (pinfunction "D_3") (pintype "passive"))
    )
    (net (code "52") (name "/K_3") (class "Default")
      (node (ref "IR3") (pin "1") (pinfunction "K_1") (pintype "passive"))
      (node (ref "Q3") (pin "3") (pinfunction "D_3") (pintype "passive"))
    )
    (net (code "53") (name "/K_4") (class "Default")
      (node (ref "IR4") (pin "1") (pinfunction "K_1") (pintype "passive"))
      (node (ref "Q4") (pin "3") (pinfunction "D_3") (pintype "passive"))
    )
    (net (code "54") (name "/K_5") (class "Default")
      (node (ref "IR5") (pin "1") (pinfunction "K_1") (pintype "passive"))
      (node (ref "Q5") (pin "3") (pinfunction "D_3") (pintype "passive"))
    )
    (net (code "55") (name "/K_6") (class "Default")
      (node (ref "IR6") (pin "1") (pinfunction "K_1") (pintype "passive"))
      (node (ref "Q6") (pin "3") (pinfunction "D_3") (pintype "passive"))
    )
    (net (code "56") (name "/LED_IN") (class "Default")
      (node (ref "U1") (pin "39") (pinfunction "PA15_39") (pintype "bidirectional"))
      (node (ref "U4") (pin "4") (pinfunction "DIN_4") (pintype "input"))
    )
    (net (code "57") (name "/MCU_BOOT0") (class "Default")
      (node (ref "R2") (pin "2") (pinfunction "2_2") (pintype "passive"))
      (node (ref "U1") (pin "45") (pinfunction "PB8-BOOT0_45") (pintype "bidirectional"))
    )
    (net (code "58") (name "/MCU_NRST") (class "Default")
      (node (ref "C10") (pin "1") (pinfunction "1_1") (pintype "passive"))
      (node (ref "J3") (pin "12") (pinfunction "12_12") (pintype "passive"))
      (node (ref "R3") (pin "2") (pinfunction "2_2") (pintype "passive"))
      (node (ref "U1") (pin "7") (pinfunction "PG10/~{RST}_7") (pintype "bidirectional"))
    )
    (net (code "59") (name "/MCU_OSC_IN") (class "Default")
      (node (ref "C8") (pin "2") (pinfunction "2_2") (pintype "passive"))
      (node (ref "U1") (pin "5") (pinfunction "PF0-OSC_IN_5") (pintype "bidirectional"))
      (node (ref "X1") (pin "1") (pinfunction "I/O_1_1") (pintype "passive"))
    )
    (net (code "60") (name "/MCU_OSC_OUT") (class "Default")
      (node (ref "R1") (pin "2") (pinfunction "2_2") (pintype "passive"))
      (node (ref "U1") (pin "6") (pinfunction "PF1-OSC_OUT_6") (pintype "bidirectional"))
    )
    (net (code "61") (name "/MCU_SWCLK") (class "Default")
      (node (ref "J3") (pin "6") (pinfunction "6_6") (pintype "passive"))
      (node (ref "U1") (pin "38") (pinfunction "PA14_38") (pintype "bidirectional"))
    )
    (net (code "62") (name "/MCU_SWDIO") (class "Default")
      (node (ref "J3") (pin "4") (pinfunction "4_4") (pintype "passive"))
      (node (ref "U1") (pin "37") (pinfunction "PA13_37") (pintype "bidirectional"))
    )
    (net (code "63") (name "/MCU_SWO") (class "Default")
      (node (ref "J3") (pin "8") (pinfunction "8_8") (pintype "passive"))
      (node (ref "U1") (pin "40") (pinfunction "PB3_40") (pintype "bidirectional"))
    )
    (net (code "64") (name "/ON_LED") (class "Default")
      (node (ref "D7") (pin "A") (pinfunction "A_A") (pintype "passive"))
      (node (ref "R8") (pin "1") (pinfunction "1_1") (pintype "passive"))
    )
    (net (code "65") (name "/OUT_1_L") (class "Default")
      (node (ref "DRV1") (pin "6") (pinfunction "OUT1_6") (pintype "passive"))
      (node (ref "J1") (pin "1") (pinfunction "1_1") (pintype "passive"))
    )
    (net (code "66") (name "/OUT_1_R") (class "Default")
      (node (ref "DRV2") (pin "6") (pinfunction "OUT1_6") (pintype "passive"))
      (node (ref "J2") (pin "1") (pinfunction "1_1") (pintype "passive"))
    )
    (net (code "67") (name "/OUT_2_L") (class "Default")
      (node (ref "DRV1") (pin "8") (pinfunction "OUT2_8") (pintype "passive"))
      (node (ref "J1") (pin "2") (pinfunction "2_2") (pintype "passive"))
    )
    (net (code "68") (name "/OUT_2_R") (class "Default")
      (node (ref "DRV2") (pin "8") (pinfunction "OUT2_8") (pintype "passive"))
      (node (ref "J2") (pin "2") (pinfunction "2_2") (pintype "passive"))
    )
    (net (code "69") (name "/UART_RX") (class "Default")
      (node (ref "J3") (pin "13") (pinfunction "13_13") (pintype "passive"))
      (node (ref "J4") (pin "3") (pinfunction "3_3") (pintype "passive"))
      (node (ref "U1") (pin "11") (pinfunction "PA3_11") (pintype "bidirectional"))
    )
    (net (code "70") (name "/UART_TX") (class "Default")
      (node (ref "J3") (pin "14") (pinfunction "14_14") (pintype "passive"))
      (node (ref "J4") (pin "4") (pinfunction "4_4") (pintype "passive"))
      (node (ref "U1") (pin "10") (pinfunction "PA2_10") (pintype "bidirectional"))
    )
    (net (code "71") (name "/VBAT_SW") (class "Default")
      (node (ref "C11") (pin "2") (pinfunction "2_2") (pintype "passive"))
      (node (ref "C12") (pin "2") (pinfunction "2_2") (pintype "passive"))
      (node (ref "R4") (pin "2") (pinfunction "2_2") (pintype "passive"))
      (node (ref "S1") (pin "2") (pinfunction "2_2") (pintype "passive"))
      (node (ref "VR1") (pin "1") (pinfunction "VIN_1") (pintype "power_in"))
    )
    (net (code "72") (name "/VDIV") (class "Default")
      (node (ref "R4") (pin "1") (pinfunction "1_1") (pintype "passive"))
      (node (ref "R5") (pin "2") (pinfunction "2_2") (pintype "passive"))
      (node (ref "VR1") (pin "6") (pinfunction "EN_6") (pintype "passive"))
    )
    (net (code "73") (name "/XTAL_IN") (class "Default")
      (node (ref "C9") (pin "2") (pinfunction "2_2") (pintype "passive"))
      (node (ref "R1") (pin "1") (pinfunction "1_1") (pintype "passive"))
      (node (ref "X1") (pin "3") (pinfunction "I/O_2_3") (pintype "passive"))
    )
    (net (code "74") (name "GND") (class "Default")
      (node (ref "C1") (pin "1") (pinfunction "1_1") (pintype "passive"))
      (node (ref "C10") (pin "2") (pinfunction "2_2") (pintype "passive"))
      (node (ref "C11") (pin "1") (pinfunction "1_1") (pintype "passive"))
      (node (ref "C12") (pin "1") (pinfunction "1_1") (pintype "passive"))
      (node (ref "C13") (pin "1") (pinfunction "1_1") (pintype "passive"))
      (node (ref "C14") (pin "1") (pinfunction "1_1") (pintype "passive"))
      (node (ref "C15") (pin "1") (pinfunction "1_1") (pintype "passive"))
      (node (ref "C16") (pin "1") (pinfunction "1_1") (pintype "passive"))
      (node (ref "C17") (pin "2") (pinfunction "N_2") (pintype "passive"))
      (node (ref "C18") (pin "2") (pinfunction "N_2") (pintype "passive"))
      (node (ref "C19") (pin "1") (pinfunction "1_1") (pintype "passive"))
      (node (ref "C2") (pin "1") (pinfunction "1_1") (pintype "passive"))
      (node (ref "C20") (pin "1") (pinfunction "1_1") (pintype "passive"))
      (node (ref "C21") (pin "2") (pinfunction "2_2") (pintype "passive"))
      (node (ref "C22") (pin "2") (pinfunction "2_2") (pintype "passive"))
      (node (ref "C3") (pin "1") (pinfunction "1_1") (pintype "passive"))
      (node (ref "C4") (pin "1") (pinfunction "1_1") (pintype "passive"))
      (node (ref "C5") (pin "1") (pinfunction "1_1") (pintype "passive"))
      (node (ref "C6") (pin "1") (pinfunction "1_1") (pintype "passive"))
      (node (ref "C7") (pin "1") (pinfunction "1_1") (pintype "passive"))
      (node (ref "C8") (pin "1") (pinfunction "1_1") (pintype "passive"))
      (node (ref "C9") (pin "1") (pinfunction "1_1") (pintype "passive"))
      (node (ref "D1") (pin "1") (pinfunction "E_1") (pintype "passive"))
      (node (ref "D2") (pin "1") (pinfunction "E_1") (pintype "passive"))
      (node (ref "D3") (pin "1") (pinfunction "E_1") (pintype "passive"))
      (node (ref "D4") (pin "1") (pinfunction "E_1") (pintype "passive"))
      (node (ref "D5") (pin "1") (pinfunction "E_1") (pintype "passive"))
      (node (ref "D6") (pin "1") (pinfunction "E_1") (pintype "passive"))
      (node (ref "D7") (pin "K") (pinfunction "K_K") (pintype "passive"))
      (node (ref "DMUX1") (pin "4") (pinfunction "~{G0}_4") (pintype "input"))
      (node (ref "DMUX1") (pin "5") (pinfunction "~{G1}_5") (pintype "input"))
      (node (ref "DMUX1") (pin "8") (pinfunction "GND_8") (pintype "power_in"))
      (node (ref "DRV1") (pin "1") (pinfunction "GND_1") (pintype "passive"))
      (node (ref "DRV1") (pin "7") (pinfunction "ISEN_7") (pintype "passive"))
      (node (ref "DRV1") (pin "9") (pinfunction "T_PAD_9") (pintype "passive"))
      (node (ref "DRV2") (pin "1") (pinfunction "GND_1") (pintype "passive"))
      (node (ref "DRV2") (pin "7") (pinfunction "ISEN_7") (pintype "passive"))
      (node (ref "DRV2") (pin "9") (pinfunction "T_PAD_9") (pintype "passive"))
      (node (ref "J1") (pin "6") (pinfunction "6_6") (pintype "passive"))
      (node (ref "J2") (pin "6") (pinfunction "6_6") (pintype "passive"))
      (node (ref "J3") (pin "11") (pinfunction "11_11") (pintype "passive"))
      (node (ref "J3") (pin "5") (pinfunction "5_5") (pintype "passive"))
      (node (ref "J3") (pin "7") (pinfunction "7_7") (pintype "passive"))
      (node (ref "J4") (pin "2") (pinfunction "2_2") (pintype "passive"))
      (node (ref "J5") (pin "2") (pinfunction "2_2") (pintype "passive"))
      (node (ref "Q1") (pin "2") (pinfunction "S_2") (pintype "passive"))
      (node (ref "Q2") (pin "2") (pinfunction "S_2") (pintype "passive"))
      (node (ref "Q3") (pin "2") (pinfunction "S_2") (pintype "passive"))
      (node (ref "Q4") (pin "2") (pinfunction "S_2") (pintype "passive"))
      (node (ref "Q5") (pin "2") (pinfunction "S_2") (pintype "passive"))
      (node (ref "Q6") (pin "2") (pinfunction "S_2") (pintype "passive"))
      (node (ref "R11") (pin "1") (pinfunction "1_1") (pintype "passive"))
      (node (ref "R14") (pin "1") (pinfunction "1_1") (pintype "passive"))
      (node (ref "R17") (pin "1") (pinfunction "1_1") (pintype "passive"))
      (node (ref "R2") (pin "1") (pinfunction "1_1") (pintype "passive"))
      (node (ref "R20") (pin "1") (pinfunction "1_1") (pintype "passive"))
      (node (ref "R23") (pin "1") (pinfunction "1_1") (pintype "passive"))
      (node (ref "R26") (pin "1") (pinfunction "1_1") (pintype "passive"))
      (node (ref "R33") (pin "1") (pinfunction "1_1") (pintype "passive"))
      (node (ref "R34") (pin "1") (pinfunction "1_1") (pintype "passive"))
      (node (ref "R35") (pin "1") (pinfunction "1_1") (pintype "passive"))
      (node (ref "R36") (pin "1") (pinfunction "1_1") (pintype "passive"))
      (node (ref "R37") (pin "1") (pinfunction "1_1") (pintype "passive"))
      (node (ref "R5") (pin "1") (pinfunction "1_1") (pintype "passive"))
      (node (ref "R7") (pin "1") (pinfunction "1_1") (pintype "passive"))
      (node (ref "U1") (pin "19") (pinfunction "VSSA_19") (pintype "power_in"))
      (node (ref "U1") (pin "23") (pinfunction "VSS_23") (pintype "power_in"))
      (node (ref "U1") (pin "35") (pinfunction "VSS_35") (pintype "power_in"))
      (node (ref "U1") (pin "47") (pinfunction "VSS_47") (pintype "power_in"))
      (node (ref "U2") (pin "2") (pinfunction "GND_2") (pintype "power_in"))
      (node (ref "U3") (pin "2") (pinfunction "SDX_2") (pintype "passive"))
      (node (ref "U3") (pin "3") (pinfunction "SCX_3") (pintype "passive"))
      (node (ref "U3") (pin "6") (pinfunction "GND_6") (pintype "power_in"))
      (node (ref "U3") (pin "7") (pinfunction "GND_7") (pintype "power_in"))
      (node (ref "U4") (pin "3") (pinfunction "VSS_3") (pintype "power_in"))
      (node (ref "VR1") (pin "4") (pinfunction "PGND_4") (pintype "power_in"))
      (node (ref "X1") (pin "2") (pinfunction "GND_1_2") (pintype "passive"))
      (node (ref "X1") (pin "4") (pinfunction "GND_2_4") (pintype "passive"))
    )
    (net (code "75") (name "VBAT") (class "Default")
      (node (ref "C17") (pin "1") (pinfunction "P_1") (pintype "passive"))
      (node (ref "C18") (pin "1") (pinfunction "P_1") (pintype "passive"))
      (node (ref "C19") (pin "2") (pinfunction "2_2") (pintype "passive"))
      (node (ref "C20") (pin "2") (pinfunction "2_2") (pintype "passive"))
      (node (ref "DRV1") (pin "5") (pinfunction "VM_5") (pintype "passive"))
      (node (ref "DRV2") (pin "5") (pinfunction "VM_5") (pintype "passive"))
      (node (ref "J5") (pin "1") (pinfunction "1_1") (pintype "passive"))
      (node (ref "S1") (pin "3") (pinfunction "3_3") (pintype "passive"))
    )
    (net (code "76") (name "unconnected-(DMUX1-Y6-Pad9)") (class "Default")
      (node (ref "DMUX1") (pin "9") (pinfunction "Y6_9") (pintype "output+no_connect"))
    )
    (net (code "77") (name "unconnected-(DMUX1-Y7-Pad7)") (class "Default")
      (node (ref "DMUX1") (pin "7") (pinfunction "Y7_7") (pintype "output+no_connect"))
    )
    (net (code "78") (name "unconnected-(J3-Pad1)") (class "Default")
      (node (ref "J3") (pin "1") (pinfunction "1_1") (pintype "passive+no_connect"))
    )
    (net (code "79") (name "unconnected-(J3-Pad2)") (class "Default")
      (node (ref "J3") (pin "2") (pinfunction "2_2") (pintype "passive+no_connect"))
    )
    (net (code "80") (name "unconnected-(J3-Pad9)") (class "Default")
      (node (ref "J3") (pin "9") (pinfunction "9_9") (pintype "passive+no_connect"))
    )
    (net (code "81") (name "unconnected-(J3-Pad10)") (class "Default")
      (node (ref "J3") (pin "10") (pinfunction "10_10") (pintype "passive+no_connect"))
    )
    (net (code "82") (name "unconnected-(S1-Pad1)") (class "Default")
      (node (ref "S1") (pin "1") (pinfunction "1_1") (pintype "passive+no_connect"))
    )
    (net (code "83") (name "unconnected-(U2-NC-Pad4)") (class "Default")
      (node (ref "U2") (pin "4") (pinfunction "NC_4") (pintype "passive+no_connect"))
    )
    (net (code "84") (name "unconnected-(U3-INT1-Pad4)") (class "Default")
      (node (ref "U3") (pin "4") (pinfunction "INT1_4") (pintype "input+no_connect"))
    )
    (net (code "85") (name "unconnected-(U3-NC-Pad10)") (class "Default")
      (node (ref "U3") (pin "10") (pinfunction "NC_10") (pintype "passive+no_connect"))
    )
    (net (code "86") (name "unconnected-(U3-NC-Pad11)") (class "Default")
      (node (ref "U3") (pin "11") (pinfunction "NC_11") (pintype "passive+no_connect"))
    )
    (net (code "87") (name "unconnected-(U4-DOUT-Pad2)") (class "Default")
      (node (ref "U4") (pin "2") (pinfunction "DOUT_2") (pintype "output+no_connect"))
    )
    (net (code "88") (name "unconnected-(VR1-PG-Pad5)") (class "Default")
      (node (ref "VR1") (pin "5") (pinfunction "PG_5") (pintype "output+no_connect"))
    )
    (net (code "89") (name "unconnected-(VR1-SW-Pad2)") (class "Default")
      (node (ref "VR1") (pin "2") (pinfunction "SW_2") (pintype "passive+no_connect"))
    )
  )
)
